# ContinuityTester.net
KiCad netlist of a schematic drawn in EAGLE
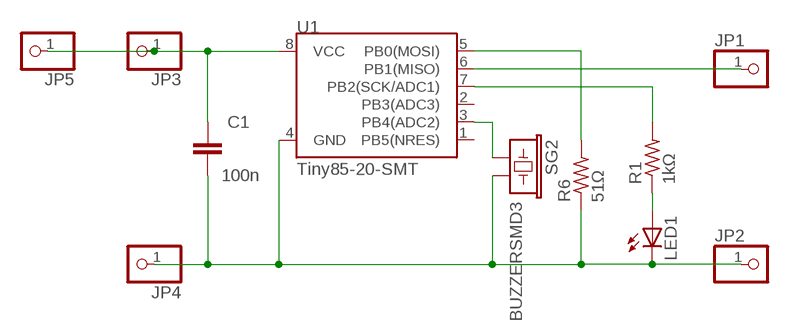
[diagram p0: schematic, sheet 1]

(export (version "E")
  (design (tool "Eeschema 10.0.6"))
  (components
    (comp (ref "C1")
      (value "100n")
      (footprint "eagle-import:0603-CAP")
      (libsource (lib "eagle-import") (part "CAP0603-CAP"))
    )
    (comp (ref "JP1")
      (value "PINHD-1X1CB")
      (footprint "eagle-import:1X01-CLEANBIG")
      (libsource (lib "eagle-import") (part "PINHD-1X1CB"))
    )
    (comp (ref "JP2")
      (value "PINHD-1X1CB")
      (footprint "eagle-import:1X01-CLEANBIG")
      (libsource (lib "eagle-import") (part "PINHD-1X1CB"))
    )
    (comp (ref "JP3")
      (value "PINHD-1X1CB")
      (footprint "eagle-import:1X01-CLEANBIG")
      (libsource (lib "eagle-import") (part "PINHD-1X1CB"))
    )
    (comp (ref "JP4")
      (value "PINHD-1X1CB")
      (footprint "eagle-import:1X01-CLEANBIG")
      (libsource (lib "eagle-import") (part "PINHD-1X1CB"))
    )
    (comp (ref "JP5")
      (value "PINHD-1X1CB")
      (footprint "eagle-import:1X01-CLEANBIG")
      (libsource (lib "eagle-import") (part "PINHD-1X1CB"))
    )
    (comp (ref "LED1")
      (value "LEDCHIPLED_0805")
      (footprint "eagle-import:CHIPLED_0805")
      (libsource (lib "eagle-import") (part "LEDCHIPLED_0805"))
    )
    (comp (ref "R1")
      (value "1kΩ")
      (footprint "eagle-import:R0805")
      (libsource (lib "eagle-import") (part "R-US_R0805"))
    )
    (comp (ref "R6")
      (value "51Ω")
      (footprint "eagle-import:R0805")
      (libsource (lib "eagle-import") (part "R-US_R0805"))
    )
    (comp (ref "SG2")
      (value "BUZZERSMD3")
      (footprint "eagle-import:BUZZER-CMT1102")
      (libsource (lib "eagle-import") (part "BUZZERSMD3"))
    )
    (comp (ref "U1")
      (value "Tiny85-20-SMT")
      (footprint "eagle-import:SO08-EIAJ")
      (libsource (lib "eagle-import") (part "ATTINY45TINY85-20-SMT"))
    )
  )
  (nets
    (net (code "1") (name "Net-(LED1-PadA)") (class "Default")
      (node (ref "LED1") (pin "A") (pinfunction "A_A") (pintype "passive"))
      (node (ref "R1") (pin "1") (pinfunction "1_1") (pintype "passive"))
    )
    (net (code "2") (name "Net-(U1-GND)") (class "Default")
      (node (ref "C1") (pin "2") (pinfunction "2_2") (pintype "passive"))
      (node (ref "JP2") (pin "1") (pinfunction "1_1") (pintype "passive"))
      (node (ref "JP4") (pin "1") (pinfunction "1_1") (pintype "passive"))
      (node (ref "LED1") (pin "C") (pinfunction "C_C") (pintype "passive"))
      (node (ref "R6") (pin "1") (pinfunction "1_1") (pintype "passive"))
      (node (ref "SG2") (pin "2") (pinfunction "2_2") (pintype "passive"))
      (node (ref "U1") (pin "4") (pinfunction "GND_4") (pintype "bidirectional"))
    )
    (net (code "3") (name "Net-(U1-PB0(MOSI))") (class "Default")
      (node (ref "R6") (pin "2") (pinfunction "2_2") (pintype "passive"))
      (node (ref "U1") (pin "5") (pinfunction "PB0(MOSI)_5") (pintype "bidirectional"))
    )
    (net (code "4") (name "Net-(U1-PB1(MISO))") (class "Default")
      (node (ref "JP1") (pin "1") (pinfunction "1_1") (pintype "passive"))
      (node (ref "U1") (pin "6") (pinfunction "PB1(MISO)_6") (pintype "bidirectional"))
    )
    (net (code "5") (name "Net-(U1-PB2(SCK{slash}ADC1))") (class "Default")
      (node (ref "R1") (pin "2") (pinfunction "2_2") (pintype "passive"))
      (node (ref "U1") (pin "7") (pinfunction "PB2(SCK/ADC1)_7") (pintype "bidirectional"))
    )
    (net (code "6") (name "Net-(U1-PB4(ADC2))") (class "Default")
      (node (ref "SG2") (pin "1") (pinfunction "1_1") (pintype "passive"))
      (node (ref "U1") (pin "3") (pinfunction "PB4(ADC2)_3") (pintype "bidirectional"))
    )
    (net (code "7") (name "Net-(U1-VCC)") (class "Default")
      (node (ref "C1") (pin "1") (pinfunction "1_1") (pintype "passive"))
      (node (ref "JP3") (pin "1") (pinfunction "1_1") (pintype "passive"))
      (node (ref "JP5") (pin "1") (pinfunction "1_1") (pintype "passive"))
      (node (ref "U1") (pin "8") (pinfunction "VCC_8") (pintype "bidirectional"))
    )
    (net (code "8") (name "unconnected-(U1-PB3(ADC3)-Pad2)") (class "Default")
      (node (ref "U1") (pin "2") (pinfunction "PB3(ADC3)_2") (pintype "bidirectional"))
    )
    (net (code "9") (name "unconnected-(U1-PB5(NRES)-Pad1)") (class "Default")
      (node (ref "U1") (pin "1") (pinfunction "PB5(NRES)_1") (pintype "bidirectional"))
    )
  )
)
